# readhead-0805.net
KiCad netlist of a schematic drawn in EAGLE
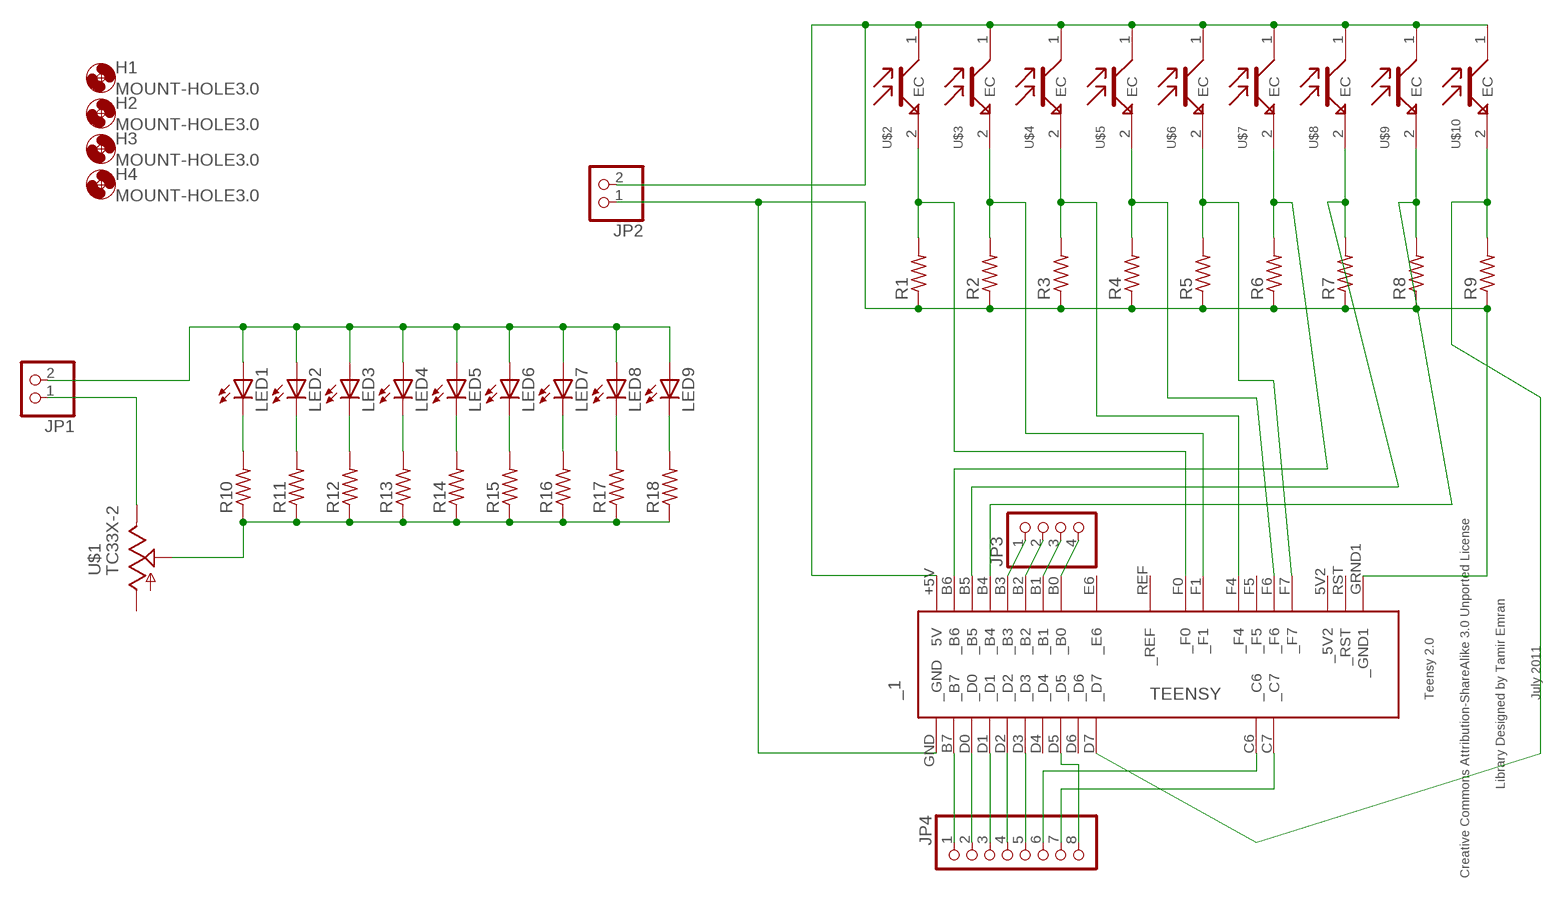
[diagram p0: schematic, sheet 1]

(export (version "E")
  (design (tool "Eeschema 10.0.6"))
  (components
    (comp (ref "H1")
      (value "MOUNT-HOLE3.0")
      (footprint "eagle-import:3,0")
      (libsource (lib "eagle-import") (part "MOUNT-HOLE3.0"))
    )
    (comp (ref "H2")
      (value "MOUNT-HOLE3.0")
      (footprint "eagle-import:3,0")
      (libsource (lib "eagle-import") (part "MOUNT-HOLE3.0"))
    )
    (comp (ref "H3")
      (value "MOUNT-HOLE3.0")
      (footprint "eagle-import:3,0")
      (libsource (lib "eagle-import") (part "MOUNT-HOLE3.0"))
    )
    (comp (ref "H4")
      (value "MOUNT-HOLE3.0")
      (footprint "eagle-import:3,0")
      (libsource (lib "eagle-import") (part "MOUNT-HOLE3.0"))
    )
    (comp (ref "JP1")
      (value "PINHD-1X2")
      (footprint "eagle-import:1X02")
      (libsource (lib "eagle-import") (part "PINHD-1X2"))
    )
    (comp (ref "JP2")
      (value "PINHD-1X2")
      (footprint "eagle-import:1X02")
      (libsource (lib "eagle-import") (part "PINHD-1X2"))
    )
    (comp (ref "JP3")
      (value "PINHD-1X4")
      (footprint "eagle-import:1X04")
      (libsource (lib "eagle-import") (part "PINHD-1X4"))
    )
    (comp (ref "JP4")
      (value "PINHD-1X8")
      (footprint "eagle-import:1X08")
      (libsource (lib "eagle-import") (part "PINHD-1X8"))
    )
    (comp (ref "LED1")
      (value "LEDCHIPLED_0805")
      (footprint "eagle-import:CHIPLED_0805")
      (libsource (lib "eagle-import") (part "LEDCHIPLED_0805"))
    )
    (comp (ref "LED2")
      (value "LEDCHIPLED_0805")
      (footprint "eagle-import:CHIPLED_0805")
      (libsource (lib "eagle-import") (part "LEDCHIPLED_0805"))
    )
    (comp (ref "LED3")
      (value "LEDCHIPLED_0805")
      (footprint "eagle-import:CHIPLED_0805")
      (libsource (lib "eagle-import") (part "LEDCHIPLED_0805"))
    )
    (comp (ref "LED4")
      (value "LEDCHIPLED_0805")
      (footprint "eagle-import:CHIPLED_0805")
      (libsource (lib "eagle-import") (part "LEDCHIPLED_0805"))
    )
    (comp (ref "LED5")
      (value "LEDCHIPLED_0805")
      (footprint "eagle-import:CHIPLED_0805")
      (libsource (lib "eagle-import") (part "LEDCHIPLED_0805"))
    )
    (comp (ref "LED6")
      (value "LEDCHIPLED_0805")
      (footprint "eagle-import:CHIPLED_0805")
      (libsource (lib "eagle-import") (part "LEDCHIPLED_0805"))
    )
    (comp (ref "LED7")
      (value "LEDCHIPLED_0805")
      (footprint "eagle-import:CHIPLED_0805")
      (libsource (lib "eagle-import") (part "LEDCHIPLED_0805"))
    )
    (comp (ref "LED8")
      (value "LEDCHIPLED_0805")
      (footprint "eagle-import:CHIPLED_0805")
      (libsource (lib "eagle-import") (part "LEDCHIPLED_0805"))
    )
    (comp (ref "LED9")
      (value "LEDCHIPLED_0805")
      (footprint "eagle-import:CHIPLED_0805")
      (libsource (lib "eagle-import") (part "LEDCHIPLED_0805"))
    )
    (comp (ref "R1")
      (value "R-US_R0805")
      (footprint "eagle-import:R0805")
      (libsource (lib "eagle-import") (part "R-US_R0805"))
    )
    (comp (ref "R2")
      (value "R-US_R0805")
      (footprint "eagle-import:R0805")
      (libsource (lib "eagle-import") (part "R-US_R0805"))
    )
    (comp (ref "R3")
      (value "R-US_R0805")
      (footprint "eagle-import:R0805")
      (libsource (lib "eagle-import") (part "R-US_R0805"))
    )
    (comp (ref "R4")
      (value "R-US_R0805")
      (footprint "eagle-import:R0805")
      (libsource (lib "eagle-import") (part "R-US_R0805"))
    )
    (comp (ref "R5")
      (value "R-US_R0805")
      (footprint "eagle-import:R0805")
      (libsource (lib "eagle-import") (part "R-US_R0805"))
    )
    (comp (ref "R6")
      (value "R-US_R0805")
      (footprint "eagle-import:R0805")
      (libsource (lib "eagle-import") (part "R-US_R0805"))
    )
    (comp (ref "R7")
      (value "R-US_R0805")
      (footprint "eagle-import:R0805")
      (libsource (lib "eagle-import") (part "R-US_R0805"))
    )
    (comp (ref "R8")
      (value "R-US_R0805")
      (footprint "eagle-import:R0805")
      (libsource (lib "eagle-import") (part "R-US_R0805"))
    )
    (comp (ref "R9")
      (value "R-US_R0805")
      (footprint "eagle-import:R0805")
      (libsource (lib "eagle-import") (part "R-US_R0805"))
    )
    (comp (ref "R10")
      (value "R-US_R0805")
      (footprint "eagle-import:R0805")
      (libsource (lib "eagle-import") (part "R-US_R0805"))
    )
    (comp (ref "R11")
      (value "R-US_R0805")
      (footprint "eagle-import:R0805")
      (libsource (lib "eagle-import") (part "R-US_R0805"))
    )
    (comp (ref "R12")
      (value "R-US_R0805")
      (footprint "eagle-import:R0805")
      (libsource (lib "eagle-import") (part "R-US_R0805"))
    )
    (comp (ref "R13")
      (value "R-US_R0805")
      (footprint "eagle-import:R0805")
      (libsource (lib "eagle-import") (part "R-US_R0805"))
    )
    (comp (ref "R14")
      (value "R-US_R0805")
      (footprint "eagle-import:R0805")
      (libsource (lib "eagle-import") (part "R-US_R0805"))
    )
    (comp (ref "R15")
      (value "R-US_R0805")
      (footprint "eagle-import:R0805")
      (libsource (lib "eagle-import") (part "R-US_R0805"))
    )
    (comp (ref "R16")
      (value "R-US_R0805")
      (footprint "eagle-import:R0805")
      (libsource (lib "eagle-import") (part "R-US_R0805"))
    )
    (comp (ref "R17")
      (value "R-US_R0805")
      (footprint "eagle-import:R0805")
      (libsource (lib "eagle-import") (part "R-US_R0805"))
    )
    (comp (ref "R18")
      (value "R-US_R0805")
      (footprint "eagle-import:R0805")
      (libsource (lib "eagle-import") (part "R-US_R0805"))
    )
    (comp (ref "U$1")
      (value "TC33X-2")
      (footprint "eagle-import:TC33X-2")
      (libsource (lib "eagle-import") (part "TC33X-2"))
    )
    (comp (ref "U$2")
      (value "OP501DA")
      (footprint "eagle-import:R0805")
      (libsource (lib "eagle-import") (part "OP501DA"))
    )
    (comp (ref "U$3")
      (value "OP501DA")
      (footprint "eagle-import:R0805")
      (libsource (lib "eagle-import") (part "OP501DA"))
    )
    (comp (ref "U$4")
      (value "OP501DA")
      (footprint "eagle-import:R0805")
      (libsource (lib "eagle-import") (part "OP501DA"))
    )
    (comp (ref "U$5")
      (value "OP501DA")
      (footprint "eagle-import:R0805")
      (libsource (lib "eagle-import") (part "OP501DA"))
    )
    (comp (ref "U$6")
      (value "OP501DA")
      (footprint "eagle-import:R0805")
      (libsource (lib "eagle-import") (part "OP501DA"))
    )
    (comp (ref "U$7")
      (value "OP501DA")
      (footprint "eagle-import:R0805")
      (libsource (lib "eagle-import") (part "OP501DA"))
    )
    (comp (ref "U$8")
      (value "OP501DA")
      (footprint "eagle-import:R0805")
      (libsource (lib "eagle-import") (part "OP501DA"))
    )
    (comp (ref "U$9")
      (value "OP501DA")
      (footprint "eagle-import:R0805")
      (libsource (lib "eagle-import") (part "OP501DA"))
    )
    (comp (ref "U$10")
      (value "OP501DA")
      (footprint "eagle-import:R0805")
      (libsource (lib "eagle-import") (part "OP501DA"))
    )
    (comp (ref "_1")
      (value "TEENSY")
      (footprint "eagle-import:TEENSY")
      (libsource (lib "eagle-import") (part "TEENSY"))
    )
  )
  (nets
    (net (code "1") (name "Net-(JP1-Pad2)") (class "Default")
      (node (ref "JP1") (pin "2") (pinfunction "2_2") (pintype "passive"))
      (node (ref "LED1") (pin "A") (pinfunction "A_A") (pintype "passive"))
      (node (ref "LED2") (pin "A") (pinfunction "A_A") (pintype "passive"))
      (node (ref "LED3") (pin "A") (pinfunction "A_A") (pintype "passive"))
      (node (ref "LED4") (pin "A") (pinfunction "A_A") (pintype "passive"))
      (node (ref "LED5") (pin "A") (pinfunction "A_A") (pintype "passive"))
      (node (ref "LED6") (pin "A") (pinfunction "A_A") (pintype "passive"))
      (node (ref "LED7") (pin "A") (pinfunction "A_A") (pintype "passive"))
      (node (ref "LED8") (pin "A") (pinfunction "A_A") (pintype "passive"))
      (node (ref "LED9") (pin "A") (pinfunction "A_A") (pintype "passive"))
    )
    (net (code "2") (name "Net-(LED1-PadC)") (class "Default")
      (node (ref "LED1") (pin "C") (pinfunction "C_C") (pintype "passive"))
      (node (ref "R10") (pin "2") (pinfunction "2_2") (pintype "passive"))
    )
    (net (code "3") (name "Net-(LED2-PadC)") (class "Default")
      (node (ref "LED2") (pin "C") (pinfunction "C_C") (pintype "passive"))
      (node (ref "R11") (pin "2") (pinfunction "2_2") (pintype "passive"))
    )
    (net (code "4") (name "Net-(LED3-PadC)") (class "Default")
      (node (ref "LED3") (pin "C") (pinfunction "C_C") (pintype "passive"))
      (node (ref "R12") (pin "2") (pinfunction "2_2") (pintype "passive"))
    )
    (net (code "5") (name "Net-(LED4-PadC)") (class "Default")
      (node (ref "LED4") (pin "C") (pinfunction "C_C") (pintype "passive"))
      (node (ref "R13") (pin "2") (pinfunction "2_2") (pintype "passive"))
    )
    (net (code "6") (name "Net-(LED5-PadC)") (class "Default")
      (node (ref "LED5") (pin "C") (pinfunction "C_C") (pintype "passive"))
      (node (ref "R14") (pin "2") (pinfunction "2_2") (pintype "passive"))
    )
    (net (code "7") (name "Net-(LED6-PadC)") (class "Default")
      (node (ref "LED6") (pin "C") (pinfunction "C_C") (pintype "passive"))
      (node (ref "R15") (pin "2") (pinfunction "2_2") (pintype "passive"))
    )
    (net (code "8") (name "Net-(LED7-PadC)") (class "Default")
      (node (ref "LED7") (pin "C") (pinfunction "C_C") (pintype "passive"))
      (node (ref "R16") (pin "2") (pinfunction "2_2") (pintype "passive"))
    )
    (net (code "9") (name "Net-(LED8-PadC)") (class "Default")
      (node (ref "LED8") (pin "C") (pinfunction "C_C") (pintype "passive"))
      (node (ref "R17") (pin "2") (pinfunction "2_2") (pintype "passive"))
    )
    (net (code "10") (name "Net-(LED9-PadC)") (class "Default")
      (node (ref "LED9") (pin "C") (pinfunction "C_C") (pintype "passive"))
      (node (ref "R18") (pin "2") (pinfunction "2_2") (pintype "passive"))
    )
    (net (code "11") (name "Net-(U$1-E)") (class "Default")
      (node (ref "JP1") (pin "1") (pinfunction "1_1") (pintype "passive"))
      (node (ref "U$1") (pin "P$3") (pinfunction "E_P$3") (pintype "passive"))
    )
    (net (code "12") (name "Net-(U$1-S)") (class "Default")
      (node (ref "R10") (pin "1") (pinfunction "1_1") (pintype "passive"))
      (node (ref "R11") (pin "1") (pinfunction "1_1") (pintype "passive"))
      (node (ref "R12") (pin "1") (pinfunction "1_1") (pintype "passive"))
      (node (ref "R13") (pin "1") (pinfunction "1_1") (pintype "passive"))
      (node (ref "R14") (pin "1") (pinfunction "1_1") (pintype "passive"))
      (node (ref "R15") (pin "1") (pinfunction "1_1") (pintype "passive"))
      (node (ref "R16") (pin "1") (pinfunction "1_1") (pintype "passive"))
      (node (ref "R17") (pin "1") (pinfunction "1_1") (pintype "passive"))
      (node (ref "R18") (pin "1") (pinfunction "1_1") (pintype "passive"))
      (node (ref "U$1") (pin "P$2") (pinfunction "S_P$2") (pintype "passive"))
    )
    (net (code "13") (name "Net-(U$2-E)") (class "Default")
      (node (ref "R1") (pin "2") (pinfunction "2_2") (pintype "passive"))
      (node (ref "U$2") (pin "2") (pinfunction "E_2") (pintype "bidirectional"))
      (node (ref "_1") (pin "F0") (pinfunction "_F0_F0") (pintype "bidirectional"))
    )
    (net (code "14") (name "Net-(U$3-E)") (class "Default")
      (node (ref "R2") (pin "2") (pinfunction "2_2") (pintype "passive"))
      (node (ref "U$3") (pin "2") (pinfunction "E_2") (pintype "bidirectional"))
      (node (ref "_1") (pin "F1") (pinfunction "_F1_F1") (pintype "bidirectional"))
    )
    (net (code "15") (name "Net-(U$4-E)") (class "Default")
      (node (ref "R3") (pin "2") (pinfunction "2_2") (pintype "passive"))
      (node (ref "U$4") (pin "2") (pinfunction "E_2") (pintype "bidirectional"))
      (node (ref "_1") (pin "F4") (pinfunction "_F4_F4") (pintype "bidirectional"))
    )
    (net (code "16") (name "Net-(U$5-E)") (class "Default")
      (node (ref "R4") (pin "2") (pinfunction "2_2") (pintype "passive"))
      (node (ref "U$5") (pin "2") (pinfunction "E_2") (pintype "bidirectional"))
      (node (ref "_1") (pin "F6") (pinfunction "_F6_F6") (pintype "bidirectional"))
    )
    (net (code "17") (name "Net-(U$6-E)") (class "Default")
      (node (ref "R5") (pin "2") (pinfunction "2_2") (pintype "passive"))
      (node (ref "U$6") (pin "2") (pinfunction "E_2") (pintype "bidirectional"))
      (node (ref "_1") (pin "F7") (pinfunction "_F7_F7") (pintype "bidirectional"))
    )
    (net (code "18") (name "Net-(U$7-E)") (class "Default")
      (node (ref "R6") (pin "2") (pinfunction "2_2") (pintype "passive"))
      (node (ref "U$7") (pin "2") (pinfunction "E_2") (pintype "bidirectional"))
      (node (ref "_1") (pin "B6") (pinfunction "_B6_B6") (pintype "bidirectional"))
    )
    (net (code "19") (name "Net-(U$8-E)") (class "Default")
      (node (ref "R7") (pin "2") (pinfunction "2_2") (pintype "passive"))
      (node (ref "U$8") (pin "2") (pinfunction "E_2") (pintype "bidirectional"))
      (node (ref "_1") (pin "B5") (pinfunction "_B5_B5") (pintype "bidirectional"))
    )
    (net (code "20") (name "Net-(U$9-E)") (class "Default")
      (node (ref "R8") (pin "2") (pinfunction "2_2") (pintype "passive"))
      (node (ref "U$9") (pin "2") (pinfunction "E_2") (pintype "bidirectional"))
      (node (ref "_1") (pin "B4") (pinfunction "_B4_B4") (pintype "bidirectional"))
    )
    (net (code "21") (name "Net-(U$10-C)") (class "Default")
      (node (ref "JP2") (pin "2") (pinfunction "2_2") (pintype "passive"))
      (node (ref "U$10") (pin "1") (pinfunction "C_1") (pintype "bidirectional"))
      (node (ref "U$2") (pin "1") (pinfunction "C_1") (pintype "bidirectional"))
      (node (ref "U$3") (pin "1") (pinfunction "C_1") (pintype "bidirectional"))
      (node (ref "U$4") (pin "1") (pinfunction "C_1") (pintype "bidirectional"))
      (node (ref "U$5") (pin "1") (pinfunction "C_1") (pintype "bidirectional"))
      (node (ref "U$6") (pin "1") (pinfunction "C_1") (pintype "bidirectional"))
      (node (ref "U$7") (pin "1") (pinfunction "C_1") (pintype "bidirectional"))
      (node (ref "U$8") (pin "1") (pinfunction "C_1") (pintype "bidirectional"))
      (node (ref "U$9") (pin "1") (pinfunction "C_1") (pintype "bidirectional"))
      (node (ref "_1") (pin "+5V") (pinfunction "5V_+5V") (pintype "bidirectional"))
    )
    (net (code "22") (name "Net-(U$10-E)") (class "Default")
      (node (ref "R9") (pin "2") (pinfunction "2_2") (pintype "passive"))
      (node (ref "U$10") (pin "2") (pinfunction "E_2") (pintype "bidirectional"))
      (node (ref "_1") (pin "D7") (pinfunction "_D7_D7") (pintype "bidirectional"))
    )
    (net (code "23") (name "Net-(_1-_B0)") (class "Default")
      (node (ref "JP3") (pin "4") (pinfunction "4_4") (pintype "passive"))
      (node (ref "_1") (pin "B0") (pinfunction "_B0_B0") (pintype "bidirectional"))
    )
    (net (code "24") (name "Net-(_1-_B1)") (class "Default")
      (node (ref "JP3") (pin "3") (pinfunction "3_3") (pintype "passive"))
      (node (ref "_1") (pin "B1") (pinfunction "_B1_B1") (pintype "bidirectional"))
    )
    (net (code "25") (name "Net-(_1-_B2)") (class "Default")
      (node (ref "JP3") (pin "2") (pinfunction "2_2") (pintype "passive"))
      (node (ref "_1") (pin "B2") (pinfunction "_B2_B2") (pintype "bidirectional"))
    )
    (net (code "26") (name "Net-(_1-_B3)") (class "Default")
      (node (ref "JP3") (pin "1") (pinfunction "1_1") (pintype "passive"))
      (node (ref "_1") (pin "B3") (pinfunction "_B3_B3") (pintype "bidirectional"))
    )
    (net (code "27") (name "Net-(_1-_B7)") (class "Default")
      (node (ref "JP4") (pin "1") (pinfunction "1_1") (pintype "passive"))
      (node (ref "_1") (pin "B7") (pinfunction "_B7_B7") (pintype "bidirectional"))
    )
    (net (code "28") (name "Net-(_1-_C6)") (class "Default")
      (node (ref "JP4") (pin "6") (pinfunction "6_6") (pintype "passive"))
      (node (ref "_1") (pin "C6") (pinfunction "_C6_C6") (pintype "bidirectional"))
    )
    (net (code "29") (name "Net-(_1-_C7)") (class "Default")
      (node (ref "JP4") (pin "7") (pinfunction "7_7") (pintype "passive"))
      (node (ref "_1") (pin "C7") (pinfunction "_C7_C7") (pintype "bidirectional"))
    )
    (net (code "30") (name "Net-(_1-_D0)") (class "Default")
      (node (ref "JP4") (pin "2") (pinfunction "2_2") (pintype "passive"))
      (node (ref "_1") (pin "D0") (pinfunction "_D0_D0") (pintype "bidirectional"))
    )
    (net (code "31") (name "Net-(_1-_D1)") (class "Default")
      (node (ref "JP4") (pin "3") (pinfunction "3_3") (pintype "passive"))
      (node (ref "_1") (pin "D1") (pinfunction "_D1_D1") (pintype "bidirectional"))
    )
    (net (code "32") (name "Net-(_1-_D2)") (class "Default")
      (node (ref "JP4") (pin "4") (pinfunction "4_4") (pintype "passive"))
      (node (ref "_1") (pin "D2") (pinfunction "_D2_D2") (pintype "bidirectional"))
    )
    (net (code "33") (name "Net-(_1-_D3)") (class "Default")
      (node (ref "JP4") (pin "5") (pinfunction "5_5") (pintype "passive"))
      (node (ref "_1") (pin "D3") (pinfunction "_D3_D3") (pintype "bidirectional"))
    )
    (net (code "34") (name "Net-(_1-_D5)") (class "Default")
      (node (ref "JP4") (pin "8") (pinfunction "8_8") (pintype "passive"))
      (node (ref "_1") (pin "D5") (pinfunction "_D5_D5") (pintype "bidirectional"))
    )
    (net (code "35") (name "Net-(_1-_GND)") (class "Default")
      (node (ref "JP2") (pin "1") (pinfunction "1_1") (pintype "passive"))
      (node (ref "R1") (pin "1") (pinfunction "1_1") (pintype "passive"))
      (node (ref "R2") (pin "1") (pinfunction "1_1") (pintype "passive"))
      (node (ref "R3") (pin "1") (pinfunction "1_1") (pintype "passive"))
      (node (ref "R4") (pin "1") (pinfunction "1_1") (pintype "passive"))
      (node (ref "R5") (pin "1") (pinfunction "1_1") (pintype "passive"))
      (node (ref "R6") (pin "1") (pinfunction "1_1") (pintype "passive"))
      (node (ref "R7") (pin "1") (pinfunction "1_1") (pintype "passive"))
      (node (ref "R8") (pin "1") (pinfunction "1_1") (pintype "passive"))
      (node (ref "R9") (pin "1") (pinfunction "1_1") (pintype "passive"))
      (node (ref "_1") (pin "GND") (pinfunction "_GND_GND") (pintype "bidirectional"))
      (node (ref "_1") (pin "GRND1") (pinfunction "_GND1_GRND1") (pintype "bidirectional"))
    )
    (net (code "36") (name "unconnected-(U$1-A-PadP$1)") (class "Default")
      (node (ref "U$1") (pin "P$1") (pinfunction "A_P$1") (pintype "passive"))
    )
    (net (code "37") (name "unconnected-(_1-_5V2-Pad5V2)") (class "Default")
      (node (ref "_1") (pin "5V2") (pinfunction "_5V2_5V2") (pintype "bidirectional"))
    )
    (net (code "38") (name "unconnected-(_1-_D4-PadD4)") (class "Default")
      (node (ref "_1") (pin "D4") (pinfunction "_D4_D4") (pintype "bidirectional"))
    )
    (net (code "39") (name "unconnected-(_1-_D6-PadD6)") (class "Default")
      (node (ref "_1") (pin "D6") (pinfunction "_D6_D6") (pintype "bidirectional"))
    )
    (net (code "40") (name "unconnected-(_1-_E6-PadE6)") (class "Default")
      (node (ref "_1") (pin "E6") (pinfunction "_E6_E6") (pintype "bidirectional"))
    )
    (net (code "41") (name "unconnected-(_1-_F5-PadF5)") (class "Default")
      (node (ref "_1") (pin "F5") (pinfunction "_F5_F5") (pintype "bidirectional"))
    )
    (net (code "42") (name "unconnected-(_1-_REF-PadREF)") (class "Default")
      (node (ref "_1") (pin "REF") (pinfunction "_REF_REF") (pintype "bidirectional"))
    )
    (net (code "43") (name "unconnected-(_1-_RST-PadRST)") (class "Default")
      (node (ref "_1") (pin "RST") (pinfunction "_RST_RST") (pintype "bidirectional"))
    )
  )
)
